# nrf24l01.net
KiCad netlist of a schematic drawn in EAGLE
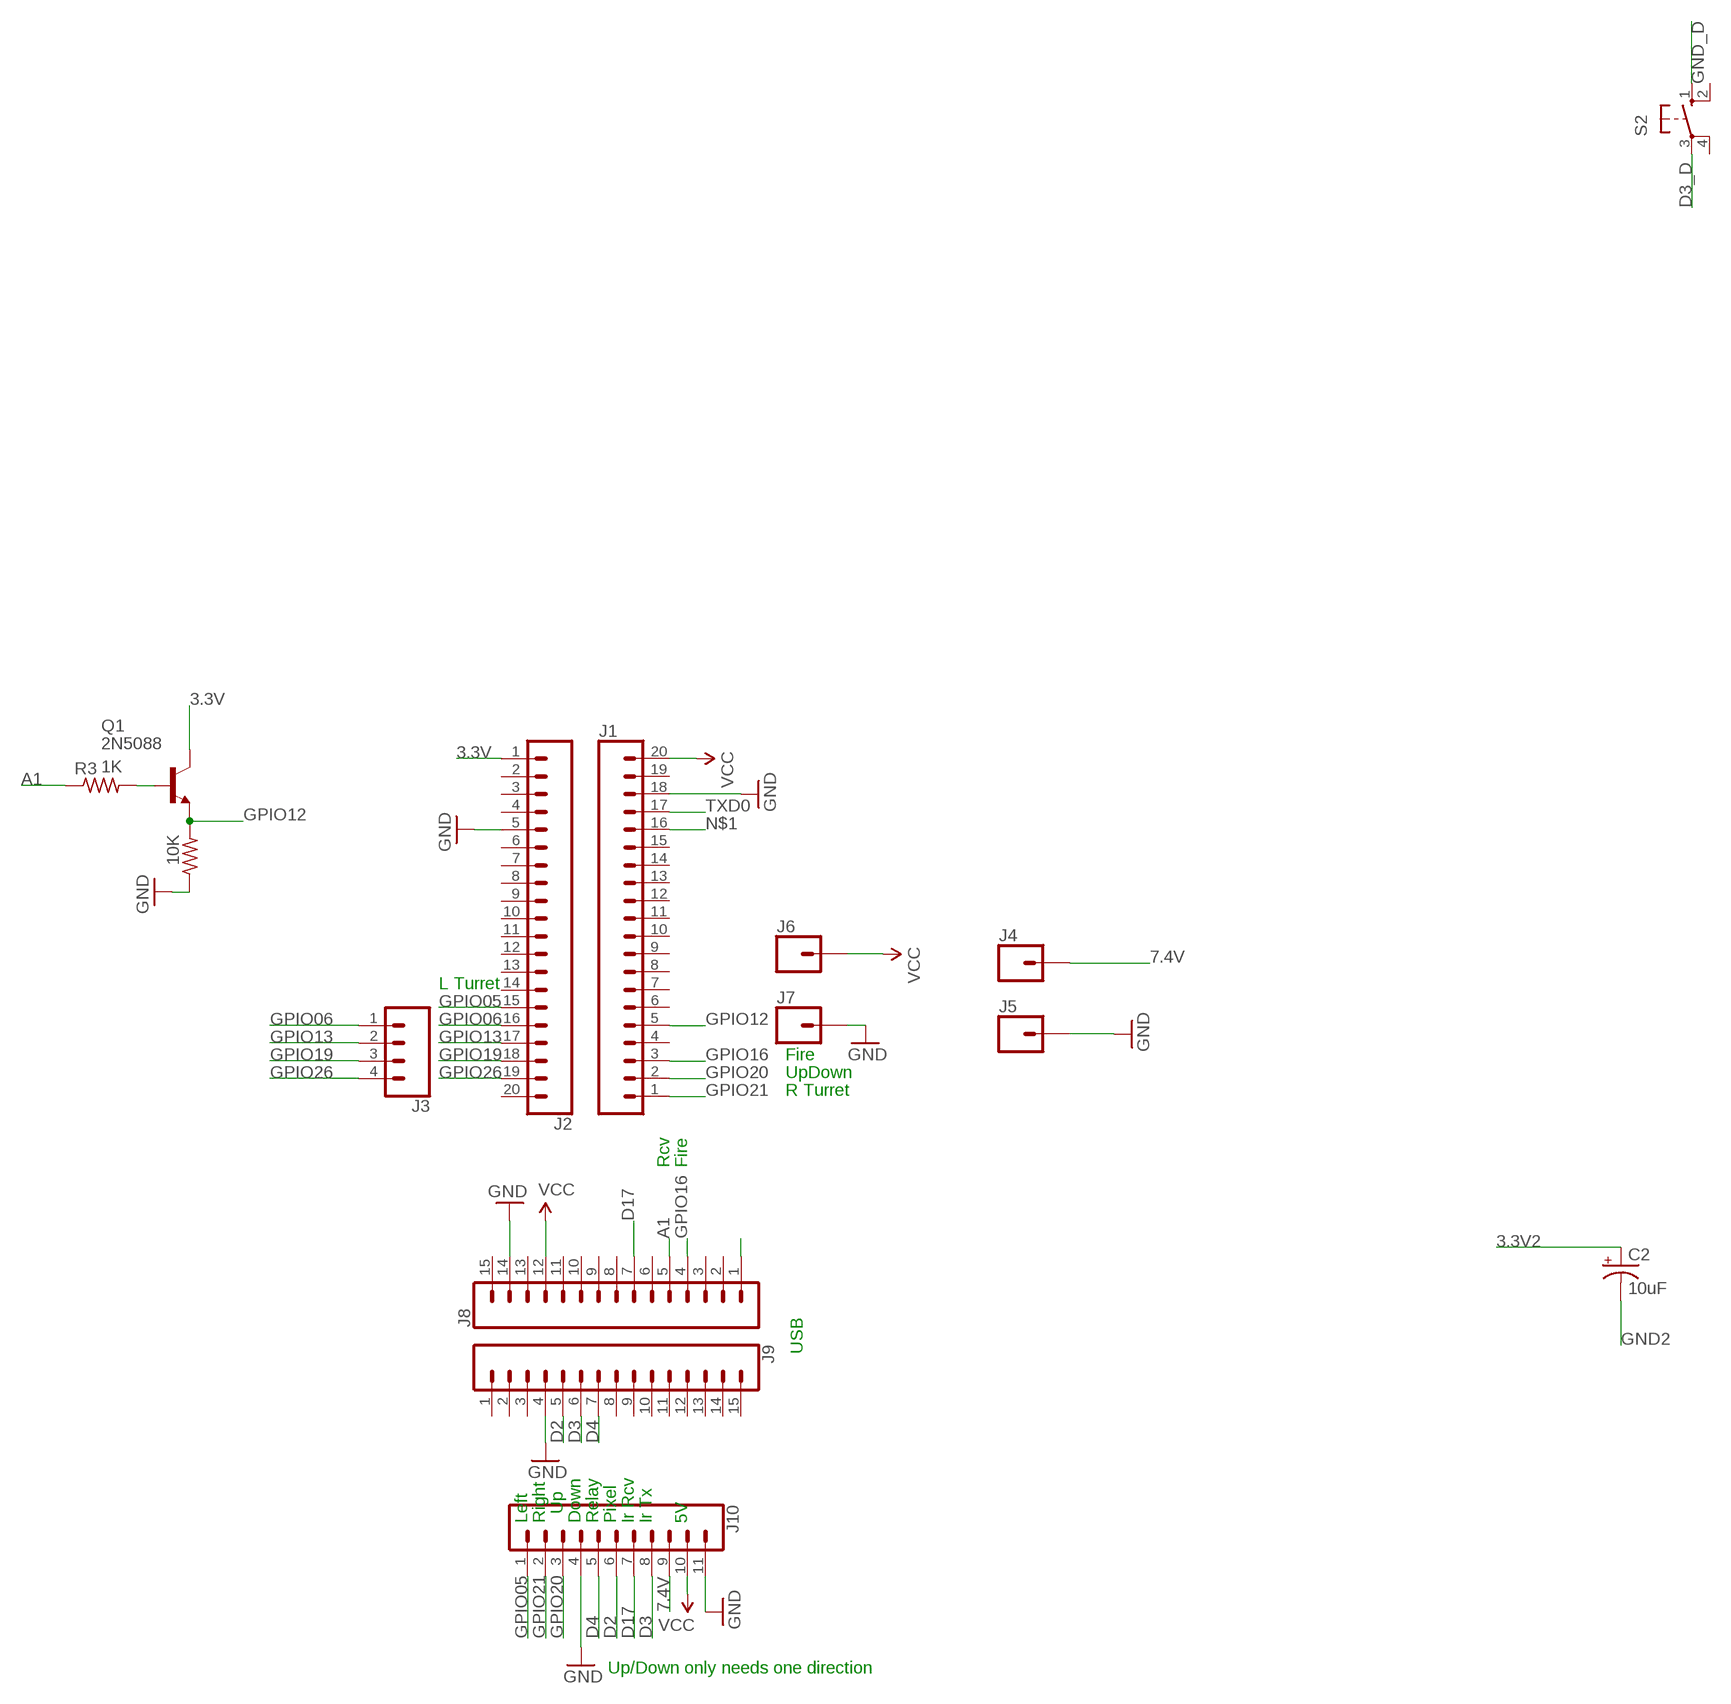
[diagram p0: schematic, sheet 1]

(export (version "E")
  (design (tool "Eeschema 10.0.6"))
  (components
    (comp (ref "10K")
      (value "10K")
      (footprint "eagle-import:0207_12")
      (libsource (lib "eagle-import") (part "R-US_0207/12"))
    )
    (comp (ref "C2")
      (value "10uF")
      (footprint "eagle-import:CPOL-RADIAL-2.5MM-5MM")
      (libsource (lib "eagle-import") (part "10UF-POLAR-RADIAL-2.5MM-25V-20%"))
    )
    (comp (ref "J1")
      (value "CONN_20")
      (footprint "eagle-import:1X20")
      (libsource (lib "eagle-import") (part "CONN_20"))
    )
    (comp (ref "J2")
      (value "CONN_20")
      (footprint "eagle-import:1X20")
      (libsource (lib "eagle-import") (part "CONN_20"))
    )
    (comp (ref "J3")
      (value "CONN_04")
      (footprint "eagle-import:1X04")
      (libsource (lib "eagle-import") (part "CONN_04"))
    )
    (comp (ref "J4")
      (value "CONN_01")
      (footprint "eagle-import:1X01")
      (libsource (lib "eagle-import") (part "CONN_01"))
    )
    (comp (ref "J5")
      (value "CONN_01")
      (footprint "eagle-import:1X01")
      (libsource (lib "eagle-import") (part "CONN_01"))
    )
    (comp (ref "J6")
      (value "CONN_01")
      (footprint "eagle-import:1X01")
      (libsource (lib "eagle-import") (part "CONN_01"))
    )
    (comp (ref "J7")
      (value "CONN_01")
      (footprint "eagle-import:1X01")
      (libsource (lib "eagle-import") (part "CONN_01"))
    )
    (comp (ref "J8")
      (value "CONN_15")
      (footprint "eagle-import:1X15")
      (libsource (lib "eagle-import") (part "CONN_15"))
    )
    (comp (ref "J9")
      (value "CONN_15")
      (footprint "eagle-import:1X15")
      (libsource (lib "eagle-import") (part "CONN_15"))
    )
    (comp (ref "J10")
      (value "CONN_11")
      (footprint "eagle-import:1X11")
      (libsource (lib "eagle-import") (part "CONN_11"))
    )
    (comp (ref "Q1")
      (value "2N5088")
      (footprint "eagle-import:TO92")
      (libsource (lib "eagle-import") (part "2N5088"))
    )
    (comp (ref "R3")
      (value "1K")
      (footprint "eagle-import:0207_12")
      (libsource (lib "eagle-import") (part "R-US_0207/12"))
    )
    (comp (ref "S2")
      (value "40-XX")
      (footprint "eagle-import:B3F-40XX")
      (fields (field (name "MF") "OMRON COMPONENTS USA") (field (name "MPN") "B3F-4000"))
      (libsource (lib "eagle-import") (part "40-XX"))
    )
  )
  (nets
    (net (code "1") (name "/3.3V") (class "Default")
      (node (ref "J2") (pin "1") (pinfunction "1_1") (pintype "passive"))
      (node (ref "Q1") (pin "1") (pinfunction "C_1") (pintype "passive"))
    )
    (net (code "2") (name "/3.3V2") (class "Default")
      (node (ref "C2") (pin "1") (pinfunction "+_1") (pintype "passive"))
    )
    (net (code "3") (name "/7.4V") (class "Default")
      (node (ref "J10") (pin "9") (pinfunction "9_9") (pintype "passive"))
      (node (ref "J4") (pin "1") (pinfunction "1_1") (pintype "passive"))
    )
    (net (code "4") (name "/A1") (class "Default")
      (node (ref "J8") (pin "5") (pinfunction "5_5") (pintype "passive"))
      (node (ref "R3") (pin "1") (pinfunction "1_1") (pintype "passive"))
    )
    (net (code "5") (name "/D2") (class "Default")
      (node (ref "J10") (pin "6") (pinfunction "6_6") (pintype "passive"))
      (node (ref "J9") (pin "5") (pinfunction "5_5") (pintype "passive"))
    )
    (net (code "6") (name "/D3") (class "Default")
      (node (ref "J10") (pin "8") (pinfunction "8_8") (pintype "passive"))
      (node (ref "J9") (pin "6") (pinfunction "6_6") (pintype "passive"))
    )
    (net (code "7") (name "/D3_D") (class "Default")
      (node (ref "S2") (pin "3") (pinfunction "P_3") (pintype "passive"))
    )
    (net (code "8") (name "/D4") (class "Default")
      (node (ref "J10") (pin "5") (pinfunction "5_5") (pintype "passive"))
      (node (ref "J9") (pin "7") (pinfunction "7_7") (pintype "passive"))
    )
    (net (code "9") (name "/D17") (class "Default")
      (node (ref "J10") (pin "7") (pinfunction "7_7") (pintype "passive"))
      (node (ref "J8") (pin "7") (pinfunction "7_7") (pintype "passive"))
    )
    (net (code "10") (name "/GND2") (class "Default")
      (node (ref "C2") (pin "2") (pinfunction "-_2") (pintype "passive"))
    )
    (net (code "11") (name "/GND_D") (class "Default")
      (node (ref "S2") (pin "1") (pinfunction "S_1") (pintype "passive"))
    )
    (net (code "12") (name "/GPIO05") (class "Default")
      (node (ref "J10") (pin "1") (pinfunction "1_1") (pintype "passive"))
      (node (ref "J2") (pin "15") (pinfunction "15_15") (pintype "passive"))
    )
    (net (code "13") (name "/GPIO06") (class "Default")
      (node (ref "J2") (pin "16") (pinfunction "16_16") (pintype "passive"))
      (node (ref "J3") (pin "1") (pinfunction "1_1") (pintype "passive"))
    )
    (net (code "14") (name "/GPIO12") (class "Default")
      (node (ref "10K") (pin "2") (pinfunction "2_2") (pintype "passive"))
      (node (ref "J1") (pin "5") (pinfunction "5_5") (pintype "passive"))
      (node (ref "Q1") (pin "3") (pinfunction "E_3") (pintype "passive"))
    )
    (net (code "15") (name "/GPIO13") (class "Default")
      (node (ref "J2") (pin "17") (pinfunction "17_17") (pintype "passive"))
      (node (ref "J3") (pin "2") (pinfunction "2_2") (pintype "passive"))
    )
    (net (code "16") (name "/GPIO16") (class "Default")
      (node (ref "J1") (pin "3") (pinfunction "3_3") (pintype "passive"))
      (node (ref "J8") (pin "4") (pinfunction "4_4") (pintype "passive"))
    )
    (net (code "17") (name "/GPIO19") (class "Default")
      (node (ref "J2") (pin "18") (pinfunction "18_18") (pintype "passive"))
      (node (ref "J3") (pin "3") (pinfunction "3_3") (pintype "passive"))
    )
    (net (code "18") (name "/GPIO20") (class "Default")
      (node (ref "J1") (pin "2") (pinfunction "2_2") (pintype "passive"))
      (node (ref "J10") (pin "3") (pinfunction "3_3") (pintype "passive"))
    )
    (net (code "19") (name "/GPIO21") (class "Default")
      (node (ref "J1") (pin "1") (pinfunction "1_1") (pintype "passive"))
      (node (ref "J10") (pin "2") (pinfunction "2_2") (pintype "passive"))
    )
    (net (code "20") (name "/GPIO26") (class "Default")
      (node (ref "J2") (pin "19") (pinfunction "19_19") (pintype "passive"))
      (node (ref "J3") (pin "4") (pinfunction "4_4") (pintype "passive"))
    )
    (net (code "21") (name "/N$1") (class "Default")
      (node (ref "J1") (pin "16") (pinfunction "16_16") (pintype "passive"))
    )
    (net (code "22") (name "/TXD0") (class "Default")
      (node (ref "J1") (pin "17") (pinfunction "17_17") (pintype "passive"))
    )
    (net (code "23") (name "GND") (class "Default")
      (node (ref "10K") (pin "1") (pinfunction "1_1") (pintype "passive"))
      (node (ref "J1") (pin "18") (pinfunction "18_18") (pintype "passive"))
      (node (ref "J10") (pin "11") (pinfunction "11_11") (pintype "passive"))
      (node (ref "J10") (pin "4") (pinfunction "4_4") (pintype "passive"))
      (node (ref "J2") (pin "5") (pinfunction "5_5") (pintype "passive"))
      (node (ref "J5") (pin "1") (pinfunction "1_1") (pintype "passive"))
      (node (ref "J7") (pin "1") (pinfunction "1_1") (pintype "passive"))
      (node (ref "J8") (pin "14") (pinfunction "14_14") (pintype "passive"))
      (node (ref "J9") (pin "4") (pinfunction "4_4") (pintype "passive"))
    )
    (net (code "24") (name "Net-(Q1-B)") (class "Default")
      (node (ref "Q1") (pin "2") (pinfunction "B_2") (pintype "passive"))
      (node (ref "R3") (pin "2") (pinfunction "2_2") (pintype "passive"))
    )
    (net (code "25") (name "VCC") (class "Default")
      (node (ref "J1") (pin "20") (pinfunction "20_20") (pintype "passive"))
      (node (ref "J10") (pin "10") (pinfunction "10_10") (pintype "passive"))
      (node (ref "J6") (pin "1") (pinfunction "1_1") (pintype "passive"))
      (node (ref "J8") (pin "12") (pinfunction "12_12") (pintype "passive"))
    )
    (net (code "26") (name "unconnected-(J1-Pad4)") (class "Default")
      (node (ref "J1") (pin "4") (pinfunction "4_4") (pintype "passive"))
    )
    (net (code "27") (name "unconnected-(J1-Pad6)") (class "Default")
      (node (ref "J1") (pin "6") (pinfunction "6_6") (pintype "passive"))
    )
    (net (code "28") (name "unconnected-(J1-Pad7)") (class "Default")
      (node (ref "J1") (pin "7") (pinfunction "7_7") (pintype "passive"))
    )
    (net (code "29") (name "unconnected-(J1-Pad8)") (class "Default")
      (node (ref "J1") (pin "8") (pinfunction "8_8") (pintype "passive"))
    )
    (net (code "30") (name "unconnected-(J1-Pad9)") (class "Default")
      (node (ref "J1") (pin "9") (pinfunction "9_9") (pintype "passive"))
    )
    (net (code "31") (name "unconnected-(J1-Pad10)") (class "Default")
      (node (ref "J1") (pin "10") (pinfunction "10_10") (pintype "passive"))
    )
    (net (code "32") (name "unconnected-(J1-Pad11)") (class "Default")
      (node (ref "J1") (pin "11") (pinfunction "11_11") (pintype "passive"))
    )
    (net (code "33") (name "unconnected-(J1-Pad12)") (class "Default")
      (node (ref "J1") (pin "12") (pinfunction "12_12") (pintype "passive"))
    )
    (net (code "34") (name "unconnected-(J1-Pad13)") (class "Default")
      (node (ref "J1") (pin "13") (pinfunction "13_13") (pintype "passive"))
    )
    (net (code "35") (name "unconnected-(J1-Pad14)") (class "Default")
      (node (ref "J1") (pin "14") (pinfunction "14_14") (pintype "passive"))
    )
    (net (code "36") (name "unconnected-(J1-Pad15)") (class "Default")
      (node (ref "J1") (pin "15") (pinfunction "15_15") (pintype "passive"))
    )
    (net (code "37") (name "unconnected-(J1-Pad19)") (class "Default")
      (node (ref "J1") (pin "19") (pinfunction "19_19") (pintype "passive"))
    )
    (net (code "38") (name "unconnected-(J2-Pad2)") (class "Default")
      (node (ref "J2") (pin "2") (pinfunction "2_2") (pintype "passive"))
    )
    (net (code "39") (name "unconnected-(J2-Pad3)") (class "Default")
      (node (ref "J2") (pin "3") (pinfunction "3_3") (pintype "passive"))
    )
    (net (code "40") (name "unconnected-(J2-Pad4)") (class "Default")
      (node (ref "J2") (pin "4") (pinfunction "4_4") (pintype "passive"))
    )
    (net (code "41") (name "unconnected-(J2-Pad6)") (class "Default")
      (node (ref "J2") (pin "6") (pinfunction "6_6") (pintype "passive"))
    )
    (net (code "42") (name "unconnected-(J2-Pad7)") (class "Default")
      (node (ref "J2") (pin "7") (pinfunction "7_7") (pintype "passive"))
    )
    (net (code "43") (name "unconnected-(J2-Pad8)") (class "Default")
      (node (ref "J2") (pin "8") (pinfunction "8_8") (pintype "passive"))
    )
    (net (code "44") (name "unconnected-(J2-Pad9)") (class "Default")
      (node (ref "J2") (pin "9") (pinfunction "9_9") (pintype "passive"))
    )
    (net (code "45") (name "unconnected-(J2-Pad10)") (class "Default")
      (node (ref "J2") (pin "10") (pinfunction "10_10") (pintype "passive"))
    )
    (net (code "46") (name "unconnected-(J2-Pad11)") (class "Default")
      (node (ref "J2") (pin "11") (pinfunction "11_11") (pintype "passive"))
    )
    (net (code "47") (name "unconnected-(J2-Pad12)") (class "Default")
      (node (ref "J2") (pin "12") (pinfunction "12_12") (pintype "passive"))
    )
    (net (code "48") (name "unconnected-(J2-Pad13)") (class "Default")
      (node (ref "J2") (pin "13") (pinfunction "13_13") (pintype "passive"))
    )
    (net (code "49") (name "unconnected-(J2-Pad14)") (class "Default")
      (node (ref "J2") (pin "14") (pinfunction "14_14") (pintype "passive"))
    )
    (net (code "50") (name "unconnected-(J2-Pad20)") (class "Default")
      (node (ref "J2") (pin "20") (pinfunction "20_20") (pintype "passive"))
    )
    (net (code "51") (name "unconnected-(J8-Pad1)") (class "Default")
      (node (ref "J8") (pin "1") (pinfunction "1_1") (pintype "passive"))
    )
    (net (code "52") (name "unconnected-(J8-Pad2)") (class "Default")
      (node (ref "J8") (pin "2") (pinfunction "2_2") (pintype "passive"))
    )
    (net (code "53") (name "unconnected-(J8-Pad3)") (class "Default")
      (node (ref "J8") (pin "3") (pinfunction "3_3") (pintype "passive"))
    )
    (net (code "54") (name "unconnected-(J8-Pad6)") (class "Default")
      (node (ref "J8") (pin "6") (pinfunction "6_6") (pintype "passive"))
    )
    (net (code "55") (name "unconnected-(J8-Pad8)") (class "Default")
      (node (ref "J8") (pin "8") (pinfunction "8_8") (pintype "passive"))
    )
    (net (code "56") (name "unconnected-(J8-Pad9)") (class "Default")
      (node (ref "J8") (pin "9") (pinfunction "9_9") (pintype "passive"))
    )
    (net (code "57") (name "unconnected-(J8-Pad10)") (class "Default")
      (node (ref "J8") (pin "10") (pinfunction "10_10") (pintype "passive"))
    )
    (net (code "58") (name "unconnected-(J8-Pad11)") (class "Default")
      (node (ref "J8") (pin "11") (pinfunction "11_11") (pintype "passive"))
    )
    (net (code "59") (name "unconnected-(J8-Pad13)") (class "Default")
      (node (ref "J8") (pin "13") (pinfunction "13_13") (pintype "passive"))
    )
    (net (code "60") (name "unconnected-(J8-Pad15)") (class "Default")
      (node (ref "J8") (pin "15") (pinfunction "15_15") (pintype "passive"))
    )
    (net (code "61") (name "unconnected-(J9-Pad1)") (class "Default")
      (node (ref "J9") (pin "1") (pinfunction "1_1") (pintype "passive"))
    )
    (net (code "62") (name "unconnected-(J9-Pad2)") (class "Default")
      (node (ref "J9") (pin "2") (pinfunction "2_2") (pintype "passive"))
    )
    (net (code "63") (name "unconnected-(J9-Pad3)") (class "Default")
      (node (ref "J9") (pin "3") (pinfunction "3_3") (pintype "passive"))
    )
    (net (code "64") (name "unconnected-(J9-Pad8)") (class "Default")
      (node (ref "J9") (pin "8") (pinfunction "8_8") (pintype "passive"))
    )
    (net (code "65") (name "unconnected-(J9-Pad9)") (class "Default")
      (node (ref "J9") (pin "9") (pinfunction "9_9") (pintype "passive"))
    )
    (net (code "66") (name "unconnected-(J9-Pad10)") (class "Default")
      (node (ref "J9") (pin "10") (pinfunction "10_10") (pintype "passive"))
    )
    (net (code "67") (name "unconnected-(J9-Pad11)") (class "Default")
      (node (ref "J9") (pin "11") (pinfunction "11_11") (pintype "passive"))
    )
    (net (code "68") (name "unconnected-(J9-Pad12)") (class "Default")
      (node (ref "J9") (pin "12") (pinfunction "12_12") (pintype "passive"))
    )
    (net (code "69") (name "unconnected-(J9-Pad13)") (class "Default")
      (node (ref "J9") (pin "13") (pinfunction "13_13") (pintype "passive"))
    )
    (net (code "70") (name "unconnected-(J9-Pad14)") (class "Default")
      (node (ref "J9") (pin "14") (pinfunction "14_14") (pintype "passive"))
    )
    (net (code "71") (name "unconnected-(J9-Pad15)") (class "Default")
      (node (ref "J9") (pin "15") (pinfunction "15_15") (pintype "passive"))
    )
    (net (code "72") (name "unconnected-(S2-P1-Pad4)") (class "Default")
      (node (ref "S2") (pin "4") (pinfunction "P1_4") (pintype "passive"))
    )
    (net (code "73") (name "unconnected-(S2-S1-Pad2)") (class "Default")
      (node (ref "S2") (pin "2") (pinfunction "S1_2") (pintype "passive"))
    )
  )
)
